# Solenoid_3.net
KiCad netlist of a schematic drawn in EAGLE
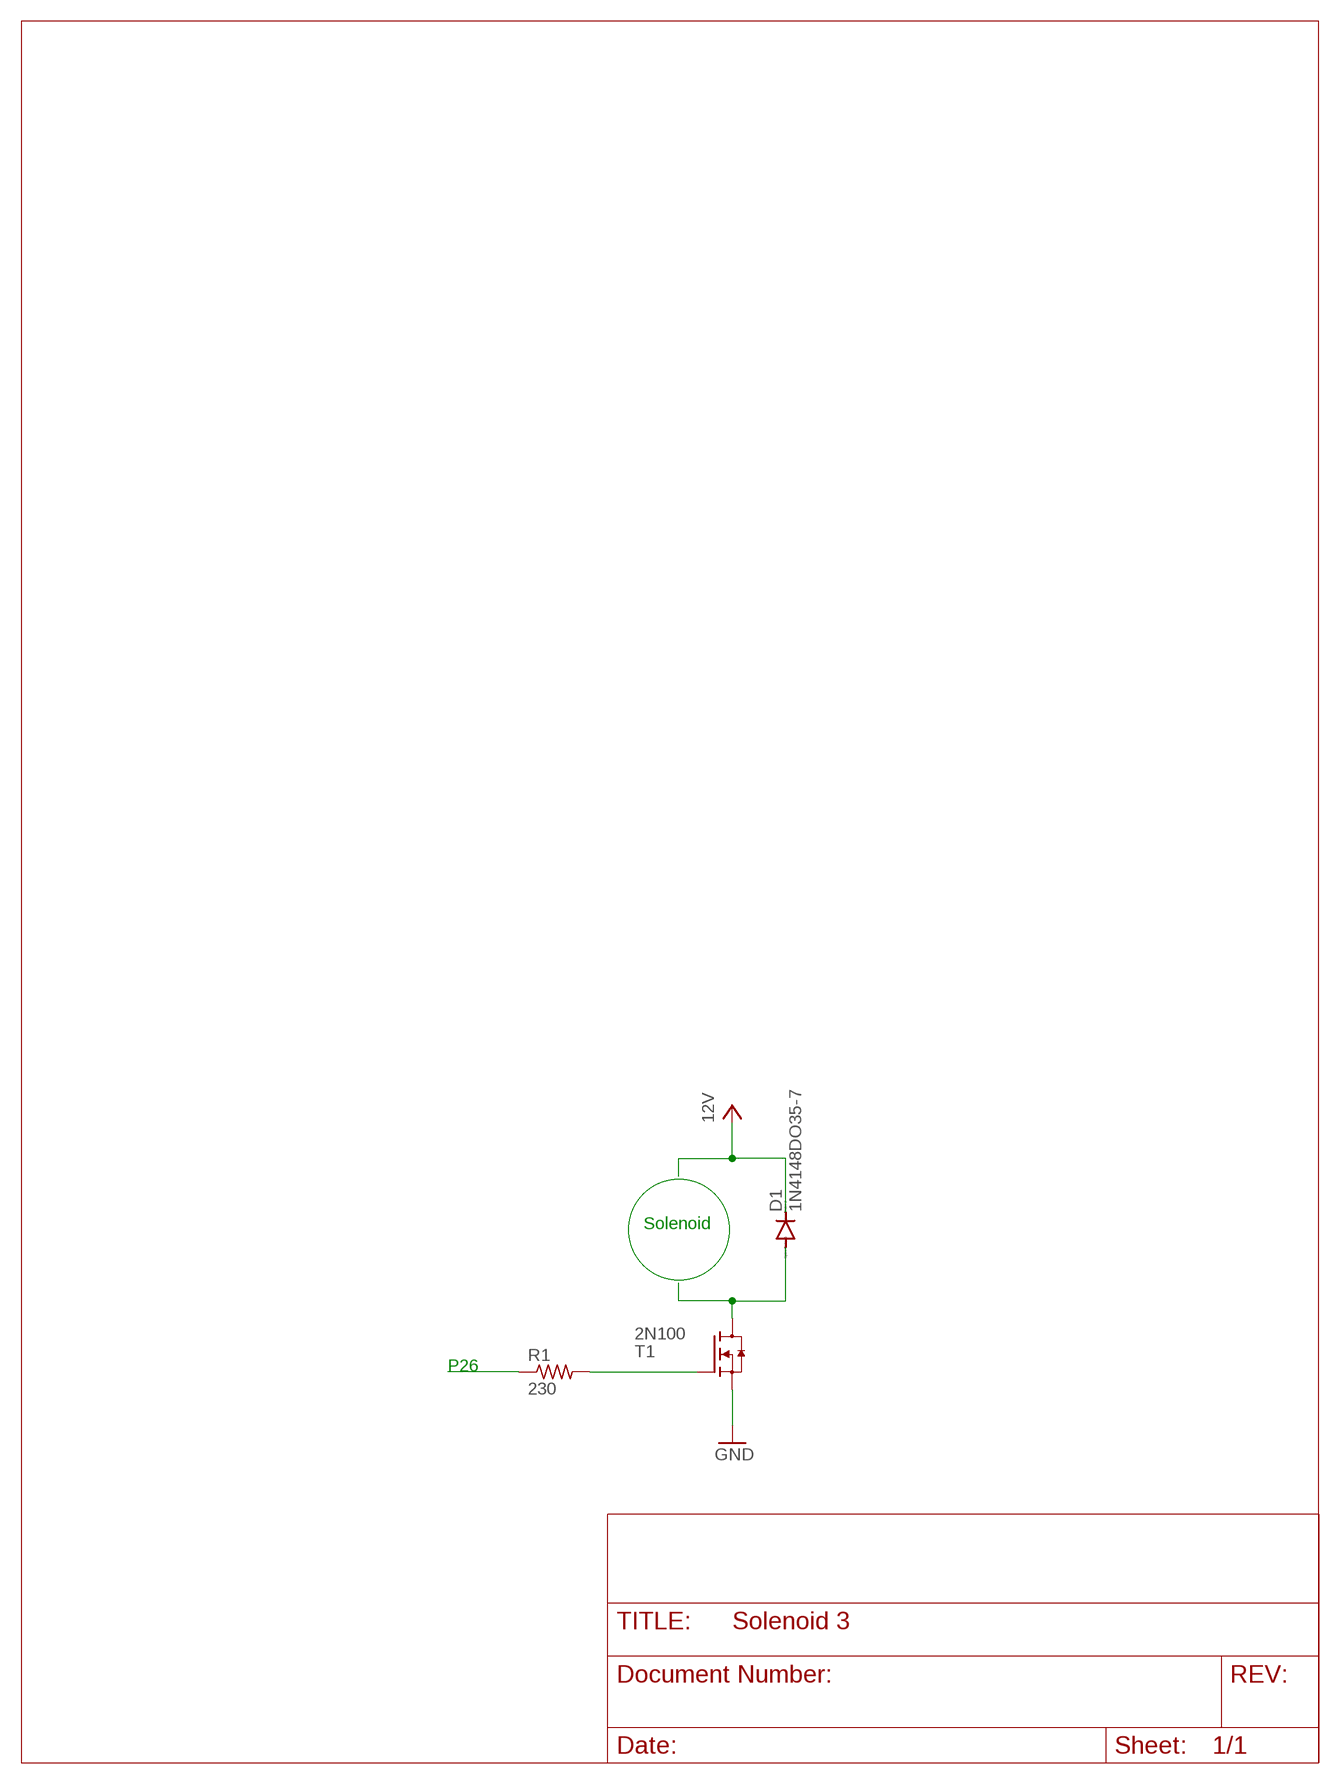
[diagram p0: schematic, sheet 1]

(export (version "E")
  (design (tool "Eeschema 10.0.6"))
  (components
    (comp (ref "D1")
      (value "1N4148DO35-7")
      (footprint "eagle-import:DO35-7")
      (libsource (lib "eagle-import") (part "1N4148DO35-7"))
    )
    (comp (ref "R1")
      (value "230")
      (footprint "eagle-import:0204_7")
      (libsource (lib "eagle-import") (part "R-US_0204/7"))
    )
    (comp (ref "T1")
      (value "2N100")
      (footprint "eagle-import:PG-TO263-7-3")
      (libsource (lib "eagle-import") (part "IPB180N06S4-H1"))
    )
  )
  (nets
    (net (code "1") (name "12V") (class "Default")
      (node (ref "D1") (pin "C") (pinfunction "C_C") (pintype "passive"))
    )
    (net (code "2") (name "GND") (class "Default")
      (node (ref "T1") (pin "2") (pinfunction "S_2") (pintype "passive"))
      (node (ref "T1") (pin "3") (pinfunction "S_3") (pintype "passive"))
      (node (ref "T1") (pin "5") (pinfunction "S_5") (pintype "passive"))
      (node (ref "T1") (pin "6") (pinfunction "S_6") (pintype "passive"))
      (node (ref "T1") (pin "7") (pinfunction "S_7") (pintype "passive"))
    )
    (net (code "3") (name "Net-(T1-D)") (class "Default")
      (node (ref "D1") (pin "A") (pinfunction "A_A") (pintype "passive"))
      (node (ref "T1") (pin "8") (pinfunction "D_8") (pintype "passive"))
    )
    (net (code "4") (name "Net-(T1-G)") (class "Default")
      (node (ref "R1") (pin "2") (pinfunction "2_2") (pintype "passive"))
      (node (ref "T1") (pin "1") (pinfunction "G_1") (pintype "passive"))
    )
    (net (code "5") (name "unconnected-(R1-Pad1)") (class "Default")
      (node (ref "R1") (pin "1") (pinfunction "1_1") (pintype "passive"))
    )
  )
)
